# Deel_2_brug_gelijkrichter.net
KiCad netlist of a schematic drawn in Altium Designer
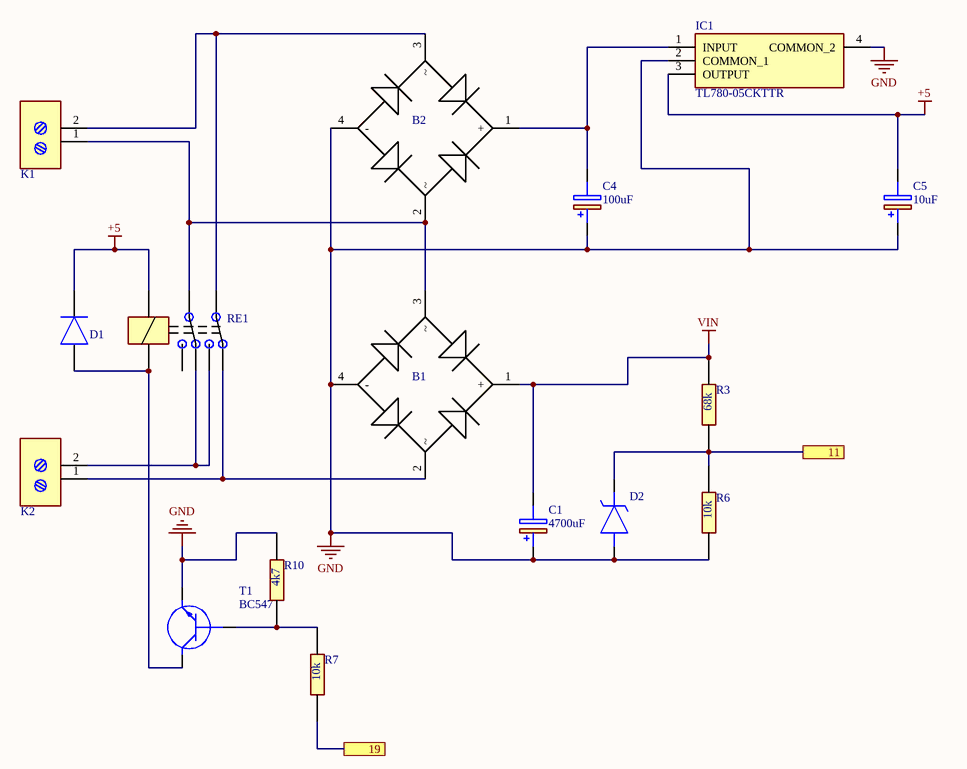
[diagram p0: Deel_2_brug_gelijkrichter.SchDoc]

(export (version "E")
  (design (tool "Eeschema 10.0.6"))
  (components
    (comp (ref "B1")
      (value "bruggelijkrichter")
      (footprint "PcbLib1:GBU606G")
      (description "Bridge Rectifier GBU606-G")
      (fields (field (name "MANUFACTURER_PART_NUMBER") "GBU606-G"))
      (libsource (lib "Schlib_soldeerstation") (part "bruggelijkrichter"))
    )
    (comp (ref "B2")
      (value "bruggelijkrichter")
      (footprint "PcbLib1:GBU606G")
      (description "Bridge Rectifier GBU606-G")
      (fields (field (name "MANUFACTURER_PART_NUMBER") "GBU606-G"))
      (libsource (lib "Schlib_soldeerstation") (part "bruggelijkrichter"))
    )
    (comp (ref "C1")
      (value "4700uF")
      (footprint "PcbLib1:4700uf")
      (description "Capacitor Polarised 50PK4700MEFC18X40")
      (fields
        (field (name "MOUSER2 PART NUMBER") "232-50PK4700MEFC18X4")
        (field (name "MANUFACTURER_PART_NUMBER") "50PK4700MEFC18X40")
      )
      (libsource (lib "Schlib_soldeerstation") (part "4700uF"))
    )
    (comp (ref "C4")
      (value "100uF")
      (footprint "PcbLib1:100uf")
      (description "Capacitor Polarised RGA101M1HBK-0811G")
      (fields (field (name "MANUFACTURER_PART_NUMBER") "RGA101M1HBK-0811G"))
      (libsource (lib "Schlib_soldeerstation") (part "100uF"))
    )
    (comp (ref "C5")
      (value "10uF")
      (footprint "PcbLib1:10uf")
      (description "Capacitor Polarised 860020672010")
      (fields
        (field (name "MOUSER2 PART NUMBER") "710-860020672010")
        (field (name "MANUFACTURER_PART_NUMBER") "860020672010")
      )
      (libsource (lib "Schlib_soldeerstation") (part "10uF"))
    )
    (comp (ref "D1")
      (value "FM4007W-W")
      (footprint "PcbLib1:fm4007")
      (description "Bridge Rectifier")
      (fields (field (name "MOUSER2 PART NUMBER") "583-FM4007W-W"))
      (libsource (lib "Schlib_soldeerstation") (part "FM4007W-W"))
    )
    (comp (ref "D2")
      (value "MMSZ4689T1G zener")
      (footprint "PcbLib1:mmsz4")
      (description "Zener Diode")
      (fields
        (field (name "MOUSER2 PART NUMBER") "863-MMSZ4689T1G")
        (field (name "MANUFACTURER_PART_NUMBER") "MMSZ4689T1G")
      )
      (libsource (lib "Schlib_soldeerstation") (part "MMSZ4689T1G zener"))
    )
    (comp (ref "IC1")
      (value "TL780-05CKTTR")
      (footprint "PcbLib1:TL78005CKTTR")
      (description "Integrated Circuit spanningsregelaar")
      (libsource (lib "Schlib_soldeerstation") (part "TL780-05CKTTR"))
    )
    (comp (ref "K1")
      (value "schroefconnector")
      (footprint "PcbLib1:schroefconnector")
      (description "Connector 1716020000")
      (fields (field (name "MANUFACTURER_PART_NUMBER") "1716020000"))
      (libsource (lib "Schlib_soldeerstation") (part "schroefconnector"))
    )
    (comp (ref "K2")
      (value "schroefconnector")
      (footprint "PcbLib1:schroefconnector")
      (description "Connector 1716020000")
      (fields (field (name "MANUFACTURER_PART_NUMBER") "1716020000"))
      (libsource (lib "Schlib_soldeerstation") (part "schroefconnector"))
    )
    (comp (ref "R3")
      (value "68k")
      (footprint "PcbLib1:68k")
      (description "Resistor")
      (fields
        (field (name "MANUFACTURER_PART_NUMBER") "CPF0805B100RE1")
        (field (name "MOUSER PART NUMBER") "279-CPF0805B100RE1")
      )
      (libsource (lib "Schlib_soldeerstation") (part "68k"))
    )
    (comp (ref "R6")
      (value "10k")
      (footprint "PcbLib1:10k")
      (description "Resistor")
      (fields
        (field (name "MANUFACTURER_PART_NUMBER") "CPF0805B100RE1")
        (field (name "MOUSER PART NUMBER") "279-CPF0805B100RE1")
      )
      (libsource (lib "Schlib_soldeerstation") (part "10k"))
    )
    (comp (ref "R7")
      (value "10k")
      (footprint "PcbLib1:10k")
      (description "Resistor")
      (fields
        (field (name "MANUFACTURER_PART_NUMBER") "CPF0805B100RE1")
        (field (name "MOUSER PART NUMBER") "279-CPF0805B100RE1")
      )
      (libsource (lib "Schlib_soldeerstation") (part "10k"))
    )
    (comp (ref "R10")
      (value "4k7")
      (footprint "PcbLib1:4k7")
      (description "Resistor")
      (fields
        (field (name "MANUFACTURER_PART_NUMBER") "CPF0805B100RE1")
        (field (name "MOUSER PART NUMBER") "279-CPF0805B100RE1")
      )
      (libsource (lib "Schlib_soldeerstation") (part "4k7"))
    )
    (comp (ref "RE1")
      (value "RT424005 relais")
      (footprint "PcbLib1:RT42005")
      (description "Relay or Contactor")
      (fields
        (field (name "MOUSER2 PART NUMBER") "655-RT424005")
        (field (name "MANUFACTURER_PART_NUMBER") "RT424005")
      )
      (libsource (lib "Schlib_soldeerstation") (part "RT424005 relais"))
    )
    (comp (ref "T1")
      (value "BC547")
      (footprint "PcbLib1:BC547CBU")
      (description "Transistor BJT NPN")
      (fields (field (name "MANUFACTURER_PART_NUMBER") "BC547CBU"))
      (libsource (lib "Schlib_soldeerstation") (part "BC547CBU"))
    )
  )
  (nets
    (net (code "1") (name "+5") (class "Default")
      (node (ref "C5") (pin "2") (pinfunction "-_2") (pintype "passive"))
      (node (ref "D1") (pin "1") (pinfunction "K_1") (pintype "passive"))
      (node (ref "IC1") (pin "3") (pinfunction "OUTPUT_3") (pintype "passive"))
      (node (ref "RE1") (pin "1") (pinfunction "A1_COIL_1") (pintype "passive"))
    )
    (net (code "2") (name "/11") (class "Default")
      (node (ref "D2") (pin "1") (pinfunction "K_1") (pintype "passive"))
      (node (ref "R3") (pin "1") (pinfunction "1_1") (pintype "passive"))
      (node (ref "R6") (pin "2") (pinfunction "2_2") (pintype "passive"))
    )
    (net (code "3") (name "/19") (class "Default")
      (node (ref "R7") (pin "1") (pinfunction "1_1") (pintype "passive"))
    )
    (net (code "4") (name "GND") (class "Default")
      (node (ref "B1") (pin "4") (pinfunction "-_4") (pintype "passive"))
      (node (ref "B2") (pin "4") (pinfunction "-_4") (pintype "passive"))
      (node (ref "C1") (pin "1") (pinfunction "+_1") (pintype "passive"))
      (node (ref "C4") (pin "1") (pinfunction "+_1") (pintype "passive"))
      (node (ref "C5") (pin "1") (pinfunction "+_1") (pintype "passive"))
      (node (ref "D2") (pin "2") (pinfunction "A_2") (pintype "passive"))
      (node (ref "IC1") (pin "2") (pinfunction "COMMON_1_2") (pintype "passive"))
      (node (ref "IC1") (pin "4") (pinfunction "COMMON_2_4") (pintype "passive"))
      (node (ref "R10") (pin "2") (pinfunction "2_2") (pintype "passive"))
      (node (ref "R6") (pin "1") (pinfunction "1_1") (pintype "passive"))
      (node (ref "T1") (pin "3") (pinfunction "E_3") (pintype "passive"))
    )
    (net (code "5") (name "Net-(B2-+)") (class "Default")
      (node (ref "B2") (pin "1") (pinfunction "+_1") (pintype "passive"))
      (node (ref "C4") (pin "2") (pinfunction "-_2") (pintype "passive"))
      (node (ref "IC1") (pin "1") (pinfunction "INPUT_1") (pintype "passive"))
    )
    (net (code "6") (name "Net-(D1-A)") (class "Default")
      (node (ref "D1") (pin "2") (pinfunction "A_2") (pintype "passive"))
      (node (ref "RE1") (pin "8") (pinfunction "A2_COIL_8") (pintype "passive"))
      (node (ref "T1") (pin "1") (pinfunction "C_1") (pintype "passive"))
    )
    (net (code "7") (name "Net-(RE1-11_COM)") (class "Default")
      (node (ref "B1") (pin "3") (pinfunction "~_3") (pintype "passive"))
      (node (ref "B2") (pin "2") (pinfunction "~_2") (pintype "passive"))
      (node (ref "K1") (pin "1") (pinfunction "1_1") (pintype "passive"))
      (node (ref "RE1") (pin "3") (pinfunction "11_COM_3") (pintype "passive"))
    )
    (net (code "8") (name "Net-(RE1-12_NC)") (class "Default")
      (node (ref "K2") (pin "2") (pinfunction "2_2") (pintype "passive"))
      (node (ref "RE1") (pin "2") (pinfunction "12_NC_2") (pintype "passive"))
      (node (ref "RE1") (pin "5") (pinfunction "24_NO_5") (pintype "passive"))
    )
    (net (code "9") (name "Net-(RE1-21_COM)") (class "Default")
      (node (ref "B2") (pin "3") (pinfunction "~_3") (pintype "passive"))
      (node (ref "K1") (pin "2") (pinfunction "2_2") (pintype "passive"))
      (node (ref "RE1") (pin "6") (pinfunction "21_COM_6") (pintype "passive"))
    )
    (net (code "10") (name "Net-(RE1-22_NC)") (class "Default")
      (node (ref "B1") (pin "2") (pinfunction "~_2") (pintype "passive"))
      (node (ref "K2") (pin "1") (pinfunction "1_1") (pintype "passive"))
      (node (ref "RE1") (pin "7") (pinfunction "22_NC_7") (pintype "passive"))
    )
    (net (code "11") (name "Net-(T1-B)") (class "Default")
      (node (ref "R10") (pin "1") (pinfunction "1_1") (pintype "passive"))
      (node (ref "R7") (pin "2") (pinfunction "2_2") (pintype "passive"))
      (node (ref "T1") (pin "2") (pinfunction "B_2") (pintype "passive"))
    )
    (net (code "12") (name "VIN") (class "Default")
      (node (ref "B1") (pin "1") (pinfunction "+_1") (pintype "passive"))
      (node (ref "C1") (pin "2") (pinfunction "-_2") (pintype "passive"))
      (node (ref "R3") (pin "2") (pinfunction "2_2") (pintype "passive"))
    )
    (net (code "13") (name "unconnected-(RE1-14_NO-Pad4)") (class "Default")
      (node (ref "RE1") (pin "4") (pinfunction "14_NO_4") (pintype "passive"))
    )
  )
)
